# 1_P1.net
KiCad netlist of a schematic drawn in Altium Designer
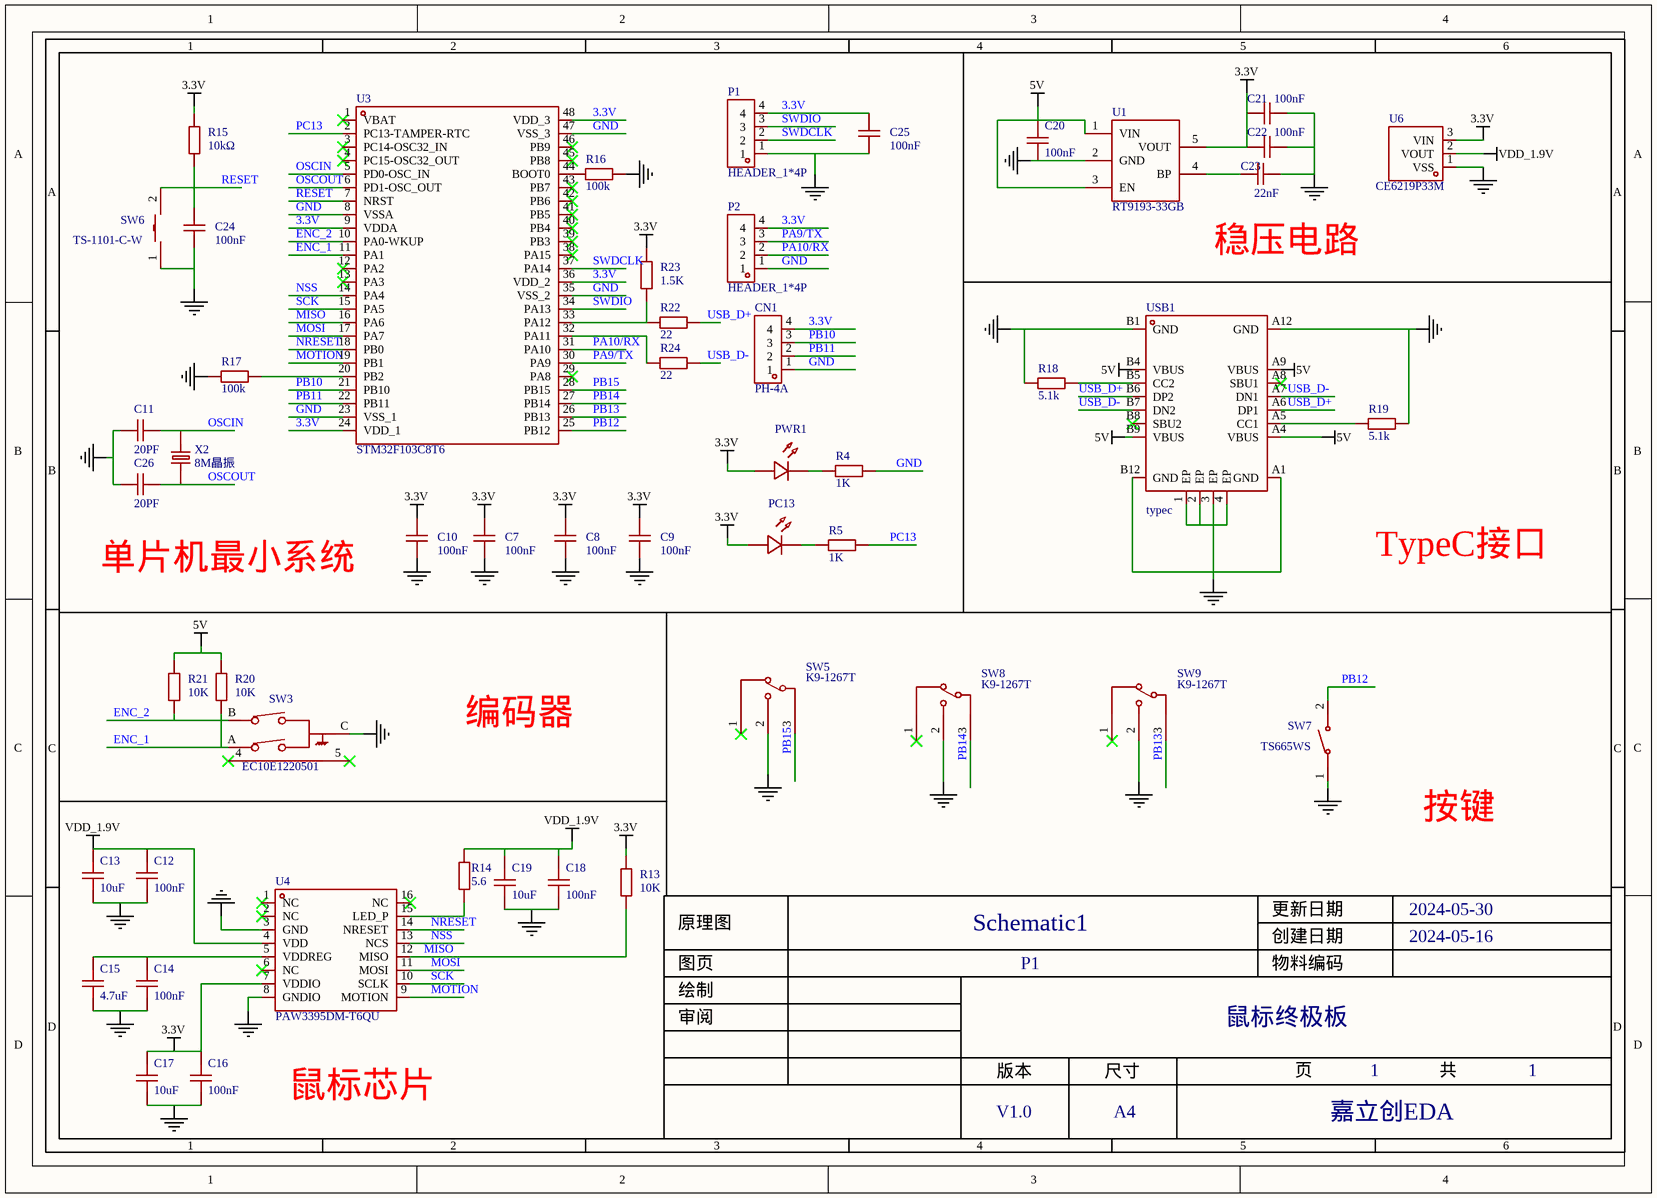
[diagram p0: 1_P1.schdoc]

(export (version "E")
  (design (tool "Eeschema 10.0.6"))
  (components
    (comp (ref "C7")
      (value "100nF")
      (description "容值:100nF;精度:±10%;额定电压:50V;材质(温度系数):X7R;")
      (fields (field (name "MANUFACTURER") "FH(风华)") (field (name "MANUFACTURER PART") "0603B104K500NT"))
      (libsource (lib "altium-import") (part "root_3_0603B104K500NT_"))
    )
    (comp (ref "C8")
      (value "100nF")
      (description "容值:100nF;精度:±10%;额定电压:50V;材质(温度系数):X7R;")
      (fields (field (name "MANUFACTURER") "FH(风华)") (field (name "MANUFACTURER PART") "0603B104K500NT"))
      (libsource (lib "altium-import") (part "root_3_0603B104K500NT_"))
    )
    (comp (ref "C9")
      (value "100nF")
      (description "容值:100nF;精度:±10%;额定电压:50V;材质(温度系数):X7R;")
      (fields (field (name "MANUFACTURER") "FH(风华)") (field (name "MANUFACTURER PART") "0603B104K500NT"))
      (libsource (lib "altium-import") (part "root_3_0603B104K500NT_"))
    )
    (comp (ref "C10")
      (value "100nF")
      (description "容值:100nF;精度:±10%;额定电压:50V;材质(温度系数):X7R;")
      (fields (field (name "MANUFACTURER") "FH(风华)") (field (name "MANUFACTURER PART") "0603B104K500NT"))
      (libsource (lib "altium-import") (part "root_3_0603B104K500NT_"))
    )
    (comp (ref "C11")
      (value "20PF")
      (description "容值:100nF;精度:±10%;额定电压:50V;材质(温度系数):X7R;")
      (fields (field (name "MANUFACTURER") "FH(风华)") (field (name "MANUFACTURER PART") "0603B104K500NT"))
      (libsource (lib "altium-import") (part "root_0_0603B104K500NT_"))
    )
    (comp (ref "C12") (value "100nF") (libsource (lib "altium-import") (part "root_1_CAP_0603_")))
    (comp (ref "C13") (value "10uF") (libsource (lib "altium-import") (part "root_1_CAP_0603_")))
    (comp (ref "C14") (value "100nF") (libsource (lib "altium-import") (part "root_1_CAP_0603_")))
    (comp (ref "C15") (value "4.7uF") (libsource (lib "altium-import") (part "root_1_CAP_0603_")))
    (comp (ref "C16") (value "100nF") (libsource (lib "altium-import") (part "root_1_CAP_0603_")))
    (comp (ref "C17") (value "10uF") (libsource (lib "altium-import") (part "root_1_CAP_0603_")))
    (comp (ref "C18") (value "100nF") (libsource (lib "altium-import") (part "root_1_CAP_0603_")))
    (comp (ref "C19") (value "10uF") (libsource (lib "altium-import") (part "root_1_CAP_0603_")))
    (comp (ref "C20")
      (value "100nF")
      (description "容值:100nF;精度:±10%;额定电压:50V;材质(温度系数):X7R;")
      (fields (field (name "MANUFACTURER") "FH(风华)") (field (name "MANUFACTURER PART") "0603B104K500NT"))
      (libsource (lib "altium-import") (part "root_1_0603B104K500NT_"))
    )
    (comp (ref "C21")
      (value "100nF")
      (description "容值:100nF;精度:±10%;额定电压:50V;材质(温度系数):X7R;")
      (fields (field (name "MANUFACTURER") "FH(风华)") (field (name "MANUFACTURER PART") "0603B104K500NT"))
      (libsource (lib "altium-import") (part "root_2_0603B104K500NT_"))
    )
    (comp (ref "C22")
      (value "100nF")
      (description "容值:100nF;精度:±10%;额定电压:50V;材质(温度系数):X7R;")
      (fields (field (name "MANUFACTURER") "FH(风华)") (field (name "MANUFACTURER PART") "0603B104K500NT"))
      (libsource (lib "altium-import") (part "root_2_0603B104K500NT_"))
    )
    (comp (ref "C23")
      (value "22nF")
      (description "容值:100nF;精度:±10%;额定电压:50V;材质(温度系数):X7R;")
      (fields (field (name "MANUFACTURER") "FH(风华)") (field (name "MANUFACTURER PART") "0603B104K500NT"))
      (libsource (lib "altium-import") (part "root_2_0603B104K500NT_"))
    )
    (comp (ref "C24")
      (value "100nF")
      (description "容值:100nF;精度:±10%;额定电压:50V;材质(温度系数):X7R;")
      (fields (field (name "MANUFACTURER") "FH(风华)") (field (name "MANUFACTURER PART") "0603B104K500NT"))
      (libsource (lib "altium-import") (part "root_1_0603B104K500NT_"))
    )
    (comp (ref "C25")
      (value "100nF")
      (description "容值:100nF;精度:±10%;额定电压:50V;材质(温度系数):X7R;")
      (fields (field (name "MANUFACTURER") "FH(风华)") (field (name "MANUFACTURER PART") "0603B104K500NT"))
      (libsource (lib "altium-import") (part "root_3_0603B104K500NT_"))
    )
    (comp (ref "C26")
      (value "20PF")
      (description "容值:100nF;精度:±10%;额定电压:50V;材质(温度系数):X7R;")
      (fields (field (name "MANUFACTURER") "FH(风华)") (field (name "MANUFACTURER PART") "0603B104K500NT"))
      (libsource (lib "altium-import") (part "root_0_0603B104K500NT_"))
    )
    (comp (ref "CN1")
      (value "PH-4A")
      (fields (field (name "MANUFACTURER") "HCTL(华灿天禄)"))
      (libsource (lib "altium-import") (part "root_2_PH-4A_C2908625_"))
    )
    (comp (ref "P1") (value "HEADER_1*4P") (libsource (lib "altium-import") (part "root_2_HEADER_1*4P_")))
    (comp (ref "P2") (value "HEADER_1*4P") (libsource (lib "altium-import") (part "root_2_HEADER_1*4P_")))
    (comp (ref "PC13") (value "LED_0603-B") (libsource (lib "altium-import") (part "root_0_LED_0603-B_")))
    (comp (ref "PWR1") (value "LED_0603-R") (libsource (lib "altium-import") (part "root_0_LED_0603-R_")))
    (comp (ref "R4")
      (value "1K")
      (description "电阻类型:厚膜电阻;阻值:10kΩ;精度:±1%;功率:100mW;")
      (fields
        (field (name "MANUFACTURER") "UNI-ROYAL(厚声)")
        (field (name "MANUFACTURER PART") "0603WAF1002T5E")
      )
      (libsource (lib "altium-import") (part "root_2_0603WAF1002T5E_"))
    )
    (comp (ref "R5")
      (value "1K")
      (description "电阻类型:厚膜电阻;阻值:10kΩ;精度:±1%;功率:100mW;")
      (fields
        (field (name "MANUFACTURER") "UNI-ROYAL(厚声)")
        (field (name "MANUFACTURER PART") "0603WAF1002T5E")
      )
      (libsource (lib "altium-import") (part "root_2_0603WAF1002T5E_"))
    )
    (comp (ref "R13") (value "10K") (libsource (lib "altium-import") (part "root_1_Res_0603_")))
    (comp (ref "R14") (value "5.6") (libsource (lib "altium-import") (part "root_1_Res_0603_")))
    (comp (ref "R15")
      (value "10kΩ")
      (description "电阻类型:厚膜电阻;阻值:10kΩ;精度:±1%;功率:100mW;")
      (fields
        (field (name "MANUFACTURER") "UNI-ROYAL(厚声)")
        (field (name "MANUFACTURER PART") "0603WAF1002T5E")
      )
      (libsource (lib "altium-import") (part "root_1_0603WAF1002T5E_"))
    )
    (comp (ref "R16")
      (value "100k")
      (description "电阻类型:厚膜电阻;阻值:10kΩ;精度:±1%;功率:100mW;")
      (fields
        (field (name "MANUFACTURER") "UNI-ROYAL(厚声)")
        (field (name "MANUFACTURER PART") "0603WAF1002T5E")
      )
      (libsource (lib "altium-import") (part "root_2_0603WAF1002T5E_"))
    )
    (comp (ref "R17")
      (value "100k")
      (description "电阻类型:厚膜电阻;阻值:10kΩ;精度:±1%;功率:100mW;")
      (fields
        (field (name "MANUFACTURER") "UNI-ROYAL(厚声)")
        (field (name "MANUFACTURER PART") "0603WAF1002T5E")
      )
      (libsource (lib "altium-import") (part "root_0_0603WAF1002T5E_"))
    )
    (comp (ref "R18") (value "5.1k") (libsource (lib "altium-import") (part "root_0_Res_0603_")))
    (comp (ref "R19") (value "5.1k") (libsource (lib "altium-import") (part "root_0_Res_0603_")))
    (comp (ref "R20") (value "10K") (libsource (lib "altium-import") (part "root_1_Res_0603_")))
    (comp (ref "R21") (value "10K") (libsource (lib "altium-import") (part "root_1_Res_0603_")))
    (comp (ref "R22")
      (value "22")
      (description "电阻类型:厚膜电阻;阻值:10kΩ;精度:±1%;功率:100mW;")
      (fields
        (field (name "MANUFACTURER") "UNI-ROYAL(厚声)")
        (field (name "MANUFACTURER PART") "0603WAF1002T5E")
      )
      (libsource (lib "altium-import") (part "root_2_0603WAF1002T5E_"))
    )
    (comp (ref "R23")
      (value "1.5K")
      (description "电阻类型:厚膜电阻;阻值:10kΩ;精度:±1%;功率:100mW;")
      (fields
        (field (name "MANUFACTURER") "UNI-ROYAL(厚声)")
        (field (name "MANUFACTURER PART") "0603WAF1002T5E")
      )
      (libsource (lib "altium-import") (part "root_3_0603WAF1002T5E_"))
    )
    (comp (ref "R24")
      (value "22")
      (description "电阻类型:厚膜电阻;阻值:10kΩ;精度:±1%;功率:100mW;")
      (fields
        (field (name "MANUFACTURER") "UNI-ROYAL(厚声)")
        (field (name "MANUFACTURER PART") "0603WAF1002T5E")
      )
      (libsource (lib "altium-import") (part "root_2_0603WAF1002T5E_"))
    )
    (comp (ref "SW3")
      (value "EC10E1220501")
      (description "10型贯通轴型")
      (fields (field (name "MANUFACTURER") "ALPSALPINE(阿尔卑斯阿尔派)"))
      (libsource (lib "altium-import") (part "root_0_EC10E1220501_"))
    )
    (comp (ref "SW5")
      (value "K9-1267T")
      (description "类型:微动开关;电路结构:单刀双掷;额定电流(DC):100mA;额定电压(DC):30V;额定电流(AC):-;额定电压(AC):-;机械寿命:300万次;")
      (fields (field (name "MANUFACTURER") "韩国韩荣"))
      (libsource (lib "altium-import") (part "root_0_K9-1267T_"))
    )
    (comp (ref "SW6")
      (value "TS-1101-C-W")
      (description "触点电流:50mA;额定电压(AC):-;额定电压(DC):12V;额定功率:-;绝缘电阻:-;电路结构:单刀单掷;安装方式:立贴;带灯:无;作用力:260gf;机械寿命:5万次;带支架:否;")
      (fields (field (name "MANUFACTURER") "XKB Connectivity(中国星坤)"))
      (libsource (lib "altium-import") (part "root_1_TS-1101-C-W_"))
    )
    (comp (ref "SW7")
      (value "TS665WS")
      (fields (field (name "MANUFACTURER") "SHOU HAN(首韩)"))
      (libsource (lib "altium-import") (part "root_1_TS665WS_C398058_"))
    )
    (comp (ref "SW8")
      (value "K9-1267T")
      (description "类型:微动开关;电路结构:单刀双掷;额定电流(DC):100mA;额定电压(DC):30V;额定电流(AC):-;额定电压(AC):-;机械寿命:300万次;")
      (fields (field (name "MANUFACTURER") "韩国韩荣"))
      (libsource (lib "altium-import") (part "root_0_K9-1267T_"))
    )
    (comp (ref "SW9")
      (value "K9-1267T")
      (description "类型:微动开关;电路结构:单刀双掷;额定电流(DC):100mA;额定电压(DC):30V;额定电流(AC):-;额定电压(AC):-;机械寿命:300万次;")
      (fields (field (name "MANUFACTURER") "韩国韩荣"))
      (libsource (lib "altium-import") (part "root_0_K9-1267T_"))
    )
    (comp (ref "U1")
      (value "RT9193-33GB")
      (description "输出类型:固定;输出极性:正;输出通道数:1;最大输入电压:5.5V;输出电压:3.3V;压差:300mV@(300mA);输出电流:300mA;电源纹波抑制比(PSRR):70dB;")
      (fields (field (name "MANUFACTURER") "RICHTEK(立锜)"))
      (libsource (lib "altium-import") (part "root_0_RT9193-33GB_"))
    )
    (comp (ref "U3")
      (value "STM32F103C8T6")
      (fields (field (name "MANUFACTURER") "ST(意法半导体)"))
      (libsource (lib "altium-import") (part "root_0_STM32F103C8T6_"))
    )
    (comp (ref "U4")
      (value "PAW3395DM-T6QU")
      (libsource (lib "altium-import") (part "root_0_PAW3395DM-T6QU_"))
    )
    (comp (ref "U6") (value "CE6219P33M") (libsource (lib "altium-import") (part "root_2_CE6219P33M_")))
    (comp (ref "USB1") (value "typec") (libsource (lib "altium-import") (part "root_0_typec_")))
    (comp (ref "X2")
      (value "8M晶振")
      (description "频率:-;负载电容:-;")
      (fields
        (field (name "MANUFACTURER") "TAITIEN(泰艺电子)")
        (field (name "MANUFACTURER PART") "XIHCELNANF-8MHZ")
      )
      (libsource (lib "altium-import") (part "root_1_XIHCELNANF-8MHZ_"))
    )
  )
  (nets
    (net (code "1") (name "/ENC_1") (class "Default")
      (node (ref "R20") (pin "1") (pinfunction "1_1") (pintype "passive"))
      (node (ref "SW3") (pin "A") (pinfunction "A_A") (pintype "passive"))
      (node (ref "U3") (pin "11") (pinfunction "PA1_11") (pintype "passive"))
    )
    (net (code "2") (name "/ENC_2") (class "Default")
      (node (ref "R21") (pin "1") (pinfunction "1_1") (pintype "passive"))
      (node (ref "SW3") (pin "B") (pinfunction "B_B") (pintype "passive"))
      (node (ref "U3") (pin "10") (pinfunction "PA0-WKUP_10") (pintype "passive"))
    )
    (net (code "3") (name "/MISO") (class "Default")
      (node (ref "R13") (pin "1") (pinfunction "1_1") (pintype "passive"))
      (node (ref "U3") (pin "16") (pinfunction "PA6_16") (pintype "passive"))
      (node (ref "U4") (pin "12") (pinfunction "MISO_12") (pintype "passive"))
    )
    (net (code "4") (name "/MOSI") (class "Default")
      (node (ref "U3") (pin "17") (pinfunction "PA7_17") (pintype "passive"))
      (node (ref "U4") (pin "11") (pinfunction "MOSI_11") (pintype "passive"))
    )
    (net (code "5") (name "/MOTION") (class "Default")
      (node (ref "U3") (pin "19") (pinfunction "PB1_19") (pintype "passive"))
      (node (ref "U4") (pin "9") (pinfunction "MOTION_9") (pintype "passive"))
    )
    (net (code "6") (name "/NRESET") (class "Default")
      (node (ref "U3") (pin "18") (pinfunction "PB0_18") (pintype "passive"))
      (node (ref "U4") (pin "14") (pinfunction "NRESET_14") (pintype "passive"))
    )
    (net (code "7") (name "/NSS") (class "Default")
      (node (ref "U3") (pin "14") (pinfunction "PA4_14") (pintype "passive"))
      (node (ref "U4") (pin "13") (pinfunction "NCS_13") (pintype "passive"))
    )
    (net (code "8") (name "/OSCIN") (class "Default")
      (node (ref "C11") (pin "2") (pinfunction "2_2") (pintype "passive"))
      (node (ref "U3") (pin "5") (pinfunction "PD0-OSC_IN_5") (pintype "passive"))
      (node (ref "X2") (pin "2") (pinfunction "2_2") (pintype "passive"))
    )
    (net (code "9") (name "/OSCOUT") (class "Default")
      (node (ref "C26") (pin "2") (pinfunction "2_2") (pintype "passive"))
      (node (ref "U3") (pin "6") (pinfunction "PD1-OSC_OUT_6") (pintype "passive"))
      (node (ref "X2") (pin "1") (pinfunction "1_1") (pintype "passive"))
    )
    (net (code "10") (name "/PA9{slash}TX") (class "Default")
      (node (ref "P2") (pin "3") (pinfunction "3_3") (pintype "passive"))
      (node (ref "U3") (pin "30") (pinfunction "PA9_30") (pintype "passive"))
    )
    (net (code "11") (name "/PA10{slash}RX") (class "Default")
      (node (ref "P2") (pin "2") (pinfunction "2_2") (pintype "passive"))
      (node (ref "U3") (pin "31") (pinfunction "PA10_31") (pintype "passive"))
    )
    (net (code "12") (name "/PB10") (class "Default")
      (node (ref "CN1") (pin "3") (pinfunction "3_3") (pintype "passive"))
      (node (ref "U3") (pin "21") (pinfunction "PB10_21") (pintype "passive"))
    )
    (net (code "13") (name "/PB11") (class "Default")
      (node (ref "CN1") (pin "2") (pinfunction "2_2") (pintype "passive"))
      (node (ref "U3") (pin "22") (pinfunction "PB11_22") (pintype "passive"))
    )
    (net (code "14") (name "/PB12") (class "Default")
      (node (ref "SW7") (pin "2") (pinfunction "B_2") (pintype "passive"))
      (node (ref "U3") (pin "25") (pinfunction "PB12_25") (pintype "passive"))
    )
    (net (code "15") (name "/PB13") (class "Default")
      (node (ref "SW9") (pin "3") (pinfunction "NC_3") (pintype "passive"))
      (node (ref "U3") (pin "26") (pinfunction "PB13_26") (pintype "passive"))
    )
    (net (code "16") (name "/PB14") (class "Default")
      (node (ref "SW8") (pin "3") (pinfunction "NC_3") (pintype "passive"))
      (node (ref "U3") (pin "27") (pinfunction "PB14_27") (pintype "passive"))
    )
    (net (code "17") (name "/PB15") (class "Default")
      (node (ref "SW5") (pin "3") (pinfunction "NC_3") (pintype "passive"))
      (node (ref "U3") (pin "28") (pinfunction "PB15_28") (pintype "passive"))
    )
    (net (code "18") (name "/PC13") (class "Default")
      (node (ref "R5") (pin "1") (pinfunction "1_1") (pintype "passive"))
      (node (ref "U3") (pin "2") (pinfunction "PC13-TAMPER-RTC_2") (pintype "passive"))
    )
    (net (code "19") (name "/RESET") (class "Default")
      (node (ref "C24") (pin "2") (pinfunction "2_2") (pintype "passive"))
      (node (ref "R15") (pin "1") (pinfunction "1_1") (pintype "passive"))
      (node (ref "SW6") (pin "2") (pinfunction "2_2") (pintype "passive"))
      (node (ref "U3") (pin "7") (pinfunction "NRST_7") (pintype "passive"))
    )
    (net (code "20") (name "/SCK") (class "Default")
      (node (ref "U3") (pin "15") (pinfunction "PA5_15") (pintype "passive"))
      (node (ref "U4") (pin "10") (pinfunction "SCLK_10") (pintype "passive"))
    )
    (net (code "21") (name "/SWDCLK") (class "Default")
      (node (ref "P1") (pin "2") (pinfunction "2_2") (pintype "passive"))
      (node (ref "U3") (pin "37") (pinfunction "PA14_37") (pintype "passive"))
    )
    (net (code "22") (name "/SWDIO") (class "Default")
      (node (ref "P1") (pin "3") (pinfunction "3_3") (pintype "passive"))
      (node (ref "U3") (pin "34") (pinfunction "PA13_34") (pintype "passive"))
    )
    (net (code "23") (name "/USB_D+") (class "Default")
      (node (ref "R22") (pin "1") (pinfunction "1_1") (pintype "passive"))
      (node (ref "USB1") (pin "A6") (pinfunction "DP1_A6") (pintype "passive"))
      (node (ref "USB1") (pin "B6") (pinfunction "DP2_B6") (pintype "passive"))
    )
    (net (code "24") (name "/USB_D-") (class "Default")
      (node (ref "R24") (pin "1") (pinfunction "1_1") (pintype "passive"))
      (node (ref "USB1") (pin "A7") (pinfunction "DN1_A7") (pintype "passive"))
      (node (ref "USB1") (pin "B7") (pinfunction "DN2_B7") (pintype "passive"))
    )
    (net (code "25") (name "3.3V") (class "Default")
      (node (ref "C10") (pin "1") (pinfunction "1_1") (pintype "passive"))
      (node (ref "C16") (pin "2") (pinfunction "2_2") (pintype "passive"))
      (node (ref "C17") (pin "2") (pinfunction "2_2") (pintype "passive"))
      (node (ref "C21") (pin "2") (pinfunction "2_2") (pintype "passive"))
      (node (ref "C22") (pin "2") (pinfunction "2_2") (pintype "passive"))
      (node (ref "C25") (pin "1") (pinfunction "1_1") (pintype "passive"))
      (node (ref "C7") (pin "1") (pinfunction "1_1") (pintype "passive"))
      (node (ref "C8") (pin "1") (pinfunction "1_1") (pintype "passive"))
      (node (ref "C9") (pin "1") (pinfunction "1_1") (pintype "passive"))
      (node (ref "CN1") (pin "4") (pinfunction "4_4") (pintype "passive"))
      (node (ref "P1") (pin "4") (pinfunction "4_4") (pintype "passive"))
      (node (ref "P2") (pin "4") (pinfunction "4_4") (pintype "passive"))
      (node (ref "PC13") (pin "2") (pinfunction "A_2") (pintype "passive"))
      (node (ref "PWR1") (pin "2") (pinfunction "A_2") (pintype "passive"))
      (node (ref "R13") (pin "2") (pinfunction "2_2") (pintype "passive"))
      (node (ref "R15") (pin "2") (pinfunction "2_2") (pintype "passive"))
      (node (ref "R23") (pin "1") (pinfunction "1_1") (pintype "passive"))
      (node (ref "U1") (pin "5") (pinfunction "VOUT_5") (pintype "passive"))
      (node (ref "U3") (pin "24") (pinfunction "VDD_1_24") (pintype "passive"))
      (node (ref "U3") (pin "36") (pinfunction "VDD_2_36") (pintype "passive"))
      (node (ref "U3") (pin "48") (pinfunction "VDD_3_48") (pintype "passive"))
      (node (ref "U3") (pin "9") (pinfunction "VDDA_9") (pintype "passive"))
      (node (ref "U4") (pin "7") (pinfunction "VDDIO_7") (pintype "passive"))
      (node (ref "U6") (pin "3") (pinfunction "VIN_3") (pintype "passive"))
    )
    (net (code "26") (name "5V") (class "Default")
      (node (ref "C20") (pin "2") (pinfunction "2_2") (pintype "passive"))
      (node (ref "R20") (pin "2") (pinfunction "2_2") (pintype "passive"))
      (node (ref "R21") (pin "2") (pinfunction "2_2") (pintype "passive"))
      (node (ref "U1") (pin "1") (pinfunction "VIN_1") (pintype "passive"))
      (node (ref "U1") (pin "3") (pinfunction "EN_3") (pintype "passive"))
      (node (ref "USB1") (pin "A4") (pinfunction "VBUS_A4") (pintype "passive"))
      (node (ref "USB1") (pin "A9") (pinfunction "VBUS_A9") (pintype "passive"))
      (node (ref "USB1") (pin "B4") (pinfunction "VBUS_B4") (pintype "passive"))
      (node (ref "USB1") (pin "B9") (pinfunction "VBUS_B9") (pintype "passive"))
    )
    (net (code "27") (name "GND") (class "Default")
      (node (ref "C10") (pin "2") (pinfunction "2_2") (pintype "passive"))
      (node (ref "C11") (pin "1") (pinfunction "1_1") (pintype "passive"))
      (node (ref "C12") (pin "1") (pinfunction "1_1") (pintype "passive"))
      (node (ref "C13") (pin "1") (pinfunction "1_1") (pintype "passive"))
      (node (ref "C14") (pin "1") (pinfunction "1_1") (pintype "passive"))
      (node (ref "C15") (pin "1") (pinfunction "1_1") (pintype "passive"))
      (node (ref "C16") (pin "1") (pinfunction "1_1") (pintype "passive"))
      (node (ref "C17") (pin "1") (pinfunction "1_1") (pintype "passive"))
      (node (ref "C18") (pin "1") (pinfunction "1_1") (pintype "passive"))
      (node (ref "C19") (pin "1") (pinfunction "1_1") (pintype "passive"))
      (node (ref "C20") (pin "1") (pinfunction "1_1") (pintype "passive"))
      (node (ref "C21") (pin "1") (pinfunction "1_1") (pintype "passive"))
      (node (ref "C22") (pin "1") (pinfunction "1_1") (pintype "passive"))
      (node (ref "C23") (pin "1") (pinfunction "1_1") (pintype "passive"))
      (node (ref "C24") (pin "1") (pinfunction "1_1") (pintype "passive"))
      (node (ref "C25") (pin "2") (pinfunction "2_2") (pintype "passive"))
      (node (ref "C26") (pin "1") (pinfunction "1_1") (pintype "passive"))
      (node (ref "C7") (pin "2") (pinfunction "2_2") (pintype "passive"))
      (node (ref "C8") (pin "2") (pinfunction "2_2") (pintype "passive"))
      (node (ref "C9") (pin "2") (pinfunction "2_2") (pintype "passive"))
      (node (ref "CN1") (pin "1") (pinfunction "1_1") (pintype "passive"))
      (node (ref "P1") (pin "1") (pinfunction "1_1") (pintype "passive"))
      (node (ref "P2") (pin "1") (pinfunction "1_1") (pintype "passive"))
      (node (ref "R16") (pin "1") (pinfunction "1_1") (pintype "passive"))
      (node (ref "R17") (pin "1") (pinfunction "1_1") (pintype "passive"))
      (node (ref "R18") (pin "1") (pinfunction "1_1") (pintype "passive"))
      (node (ref "R19") (pin "2") (pinfunction "2_2") (pintype "passive"))
      (node (ref "R4") (pin "1") (pinfunction "1_1") (pintype "passive"))
      (node (ref "SW3") (pin "C") (pinfunction "C_C") (pintype "passive"))
      (node (ref "SW5") (pin "2") (pinfunction "ON_2") (pintype "passive"))
      (node (ref "SW6") (pin "1") (pinfunction "1_1") (pintype "passive"))
      (node (ref "SW7") (pin "1") (pinfunction "A_1") (pintype "passive"))
      (node (ref "SW8") (pin "2") (pinfunction "ON_2") (pintype "passive"))
      (node (ref "SW9") (pin "2") (pinfunction "ON_2") (pintype "passive"))
      (node (ref "U1") (pin "2") (pinfunction "GND_2") (pintype "passive"))
      (node (ref "U3") (pin "23") (pinfunction "VSS_1_23") (pintype "passive"))
      (node (ref "U3") (pin "35") (pinfunction "VSS_2_35") (pintype "passive"))
      (node (ref "U3") (pin "47") (pinfunction "VSS_3_47") (pintype "passive"))
      (node (ref "U3") (pin "8") (pinfunction "VSSA_8") (pintype "passive"))
      (node (ref "U4") (pin "3") (pinfunction "GND_3") (pintype "passive"))
      (node (ref "U4") (pin "8") (pinfunction "GNDIO_8") (pintype "passive"))
      (node (ref "U6") (pin "1") (pinfunction "VSS_1") (pintype "passive"))
      (node (ref "USB1") (pin "1") (pinfunction "EP_1") (pintype "passive"))
      (node (ref "USB1") (pin "2") (pinfunction "EP_2") (pintype "passive"))
      (node (ref "USB1") (pin "3") (pinfunction "EP_3") (pintype "passive"))
      (node (ref "USB1") (pin "4") (pinfunction "EP_4") (pintype "passive"))
      (node (ref "USB1") (pin "A1") (pinfunction "GND_A1") (pintype "passive"))
      (node (ref "USB1") (pin "A12") (pinfunction "GND_A12") (pintype "passive"))
      (node (ref "USB1") (pin "B1") (pinfunction "GND_B1") (pintype "passive"))
      (node (ref "USB1") (pin "B12") (pinfunction "GND_B12") (pintype "passive"))
    )
    (net (code "28") (name "Net-(PC13-C)") (class "Default")
      (node (ref "PC13") (pin "1") (pinfunction "C_1") (pintype "passive"))
      (node (ref "R5") (pin "2") (pinfunction "2_2") (pintype "passive"))
    )
    (net (code "29") (name "Net-(PWR1-C)") (class "Default")
      (node (ref "PWR1") (pin "1") (pinfunction "C_1") (pintype "passive"))
      (node (ref "R4") (pin "2") (pinfunction "2_2") (pintype "passive"))
    )
    (net (code "30") (name "Net-(U1-BP)") (class "Default")
      (node (ref "C23") (pin "2") (pinfunction "2_2") (pintype "passive"))
      (node (ref "U1") (pin "4") (pinfunction "BP_4") (pintype "passive"))
    )
    (net (code "31") (name "Net-(U3-BOOT0)") (class "Default")
      (node (ref "R16") (pin "2") (pinfunction "2_2") (pintype "passive"))
      (node (ref "U3") (pin "44") (pinfunction "BOOT0_44") (pintype "passive"))
    )
    (net (code "32") (name "Net-(U3-PA11)") (class "Default")
      (node (ref "R24") (pin "2") (pinfunction "2_2") (pintype "passive"))
      (node (ref "U3") (pin "32") (pinfunction "PA11_32") (pintype "passive"))
    )
    (net (code "33") (name "Net-(U3-PA12)") (class "Default")
      (node (ref "R22") (pin "2") (pinfunction "2_2") (pintype "passive"))
      (node (ref "R23") (pin "2") (pinfunction "2_2") (pintype "passive"))
      (node (ref "U3") (pin "33") (pinfunction "PA12_33") (pintype "passive"))
    )
    (net (code "34") (name "Net-(U3-PB2)") (class "Default")
      (node (ref "R17") (pin "2") (pinfunction "2_2") (pintype "passive"))
      (node (ref "U3") (pin "20") (pinfunction "PB2_20") (pintype "passive"))
    )
    (net (code "35") (name "Net-(U4-LED_P)") (class "Default")
      (node (ref "R14") (pin "1") (pinfunction "1_1") (pintype "passive"))
      (node (ref "U4") (pin "15") (pinfunction "LED_P_15") (pintype "passive"))
    )
    (net (code "36") (name "Net-(U4-VDDREG)") (class "Default")
      (node (ref "C14") (pin "2") (pinfunction "2_2") (pintype "passive"))
      (node (ref "C15") (pin "2") (pinfunction "2_2") (pintype "passive"))
      (node (ref "U4") (pin "5") (pinfunction "VDDREG_5") (pintype "passive"))
    )
    (net (code "37") (name "Net-(USB1-CC1)") (class "Default")
      (node (ref "R19") (pin "1") (pinfunction "1_1") (pintype "passive"))
      (node (ref "USB1") (pin "A5") (pinfunction "CC1_A5") (pintype "passive"))
    )
    (net (code "38") (name "Net-(USB1-CC2)") (class "Default")
      (node (ref "R18") (pin "2") (pinfunction "2_2") (pintype "passive"))
      (node (ref "USB1") (pin "B5") (pinfunction "CC2_B5") (pintype "passive"))
    )
    (net (code "39") (name "VDD_1.9V") (class "Default")
      (node (ref "C12") (pin "2") (pinfunction "2_2") (pintype "passive"))
      (node (ref "C13") (pin "2") (pinfunction "2_2") (pintype "passive"))
      (node (ref "C18") (pin "2") (pinfunction "2_2") (pintype "passive"))
      (node (ref "C19") (pin "2") (pinfunction "2_2") (pintype "passive"))
      (node (ref "R14") (pin "2") (pinfunction "2_2") (pintype "passive"))
      (node (ref "U4") (pin "4") (pinfunction "VDD_4") (pintype "passive"))
      (node (ref "U6") (pin "2") (pinfunction "VOUT_2") (pintype "passive"))
    )
    (net (code "40") (name "unconnected-(SW3-Pad4)") (class "Default")
      (node (ref "SW3") (pin "4") (pinfunction "4_4") (pintype "passive+no_connect"))
    )
    (net (code "41") (name "unconnected-(SW3-Pad5)") (class "Default")
      (node (ref "SW3") (pin "5") (pinfunction "5_5") (pintype "passive+no_connect"))
    )
    (net (code "42") (name "unconnected-(SW5-C-Pad1)") (class "Default")
      (node (ref "SW5") (pin "1") (pinfunction "C_1") (pintype "passive+no_connect"))
    )
    (net (code "43") (name "unconnected-(SW8-C-Pad1)") (class "Default")
      (node (ref "SW8") (pin "1") (pinfunction "C_1") (pintype "passive+no_connect"))
    )
    (net (code "44") (name "unconnected-(SW9-C-Pad1)") (class "Default")
      (node (ref "SW9") (pin "1") (pinfunction "C_1") (pintype "passive+no_connect"))
    )
    (net (code "45") (name "unconnected-(U3-PA2-Pad12)") (class "Default")
      (node (ref "U3") (pin "12") (pinfunction "PA2_12") (pintype "passive+no_connect"))
    )
    (net (code "46") (name "unconnected-(U3-PA3-Pad13)") (class "Default")
      (node (ref "U3") (pin "13") (pinfunction "PA3_13") (pintype "passive+no_connect"))
    )
    (net (code "47") (name "unconnected-(U3-PA8-Pad29)") (class "Default")
      (node (ref "U3") (pin "29") (pinfunction "PA8_29") (pintype "passive+no_connect"))
    )
    (net (code "48") (name "unconnected-(U3-PA15-Pad38)") (class "Default")
      (node (ref "U3") (pin "38") (pinfunction "PA15_38") (pintype "passive+no_connect"))
    )
    (net (code "49") (name "unconnected-(U3-PB3-Pad39)") (class "Default")
      (node (ref "U3") (pin "39") (pinfunction "PB3_39") (pintype "passive+no_connect"))
    )
    (net (code "50") (name "unconnected-(U3-PB4-Pad40)") (class "Default")
      (node (ref "U3") (pin "40") (pinfunction "PB4_40") (pintype "passive+no_connect"))
    )
    (net (code "51") (name "unconnected-(U3-PB5-Pad41)") (class "Default")
      (node (ref "U3") (pin "41") (pinfunction "PB5_41") (pintype "passive+no_connect"))
    )
    (net (code "52") (name "unconnected-(U3-PB6-Pad42)") (class "Default")
      (node (ref "U3") (pin "42") (pinfunction "PB6_42") (pintype "passive+no_connect"))
    )
    (net (code "53") (name "unconnected-(U3-PB7-Pad43)") (class "Default")
      (node (ref "U3") (pin "43") (pinfunction "PB7_43") (pintype "passive+no_connect"))
    )
    (net (code "54") (name "unconnected-(U3-PB8-Pad45)") (class "Default")
      (node (ref "U3") (pin "45") (pinfunction "PB8_45") (pintype "passive+no_connect"))
    )
    (net (code "55") (name "unconnected-(U3-PB9-Pad46)") (class "Default")
      (node (ref "U3") (pin "46") (pinfunction "PB9_46") (pintype "passive+no_connect"))
    )
    (net (code "56") (name "unconnected-(U3-PC14-OSC32_IN-Pad3)") (class "Default")
      (node (ref "U3") (pin "3") (pinfunction "PC14-OSC32_IN_3") (pintype "passive+no_connect"))
    )
    (net (code "57") (name "unconnected-(U3-PC15-OSC32_OUT-Pad4)") (class "Default")
      (node (ref "U3") (pin "4") (pinfunction "PC15-OSC32_OUT_4") (pintype "passive+no_connect"))
    )
    (net (code "58") (name "unconnected-(U3-VBAT-Pad1)") (class "Default")
      (node (ref "U3") (pin "1") (pinfunction "VBAT_1") (pintype "passive+no_connect"))
    )
    (net (code "59") (name "unconnected-(U4-NC-Pad1)") (class "Default")
      (node (ref "U4") (pin "1") (pinfunction "NC_1") (pintype "passive+no_connect"))
    )
    (net (code "60") (name "unconnected-(U4-NC-Pad2)") (class "Default")
      (node (ref "U4") (pin "2") (pinfunction "NC_2") (pintype "passive+no_connect"))
    )
    (net (code "61") (name "unconnected-(U4-NC-Pad6)") (class "Default")
      (node (ref "U4") (pin "6") (pinfunction "NC_6") (pintype "passive+no_connect"))
    )
    (net (code "62") (name "unconnected-(U4-NC-Pad16)") (class "Default")
      (node (ref "U4") (pin "16") (pinfunction "NC_16") (pintype "passive+no_connect"))
    )
    (net (code "63") (name "unconnected-(USB1-SBU1-PadA8)") (class "Default")
      (node (ref "USB1") (pin "A8") (pinfunction "SBU1_A8") (pintype "passive+no_connect"))
    )
    (net (code "64") (name "unconnected-(USB1-SBU2-PadB8)") (class "Default")
      (node (ref "USB1") (pin "B8") (pinfunction "SBU2_B8") (pintype "passive+no_connect"))
    )
  )
)
